# Proto_Pi.net
KiCad netlist of a schematic drawn in EAGLE
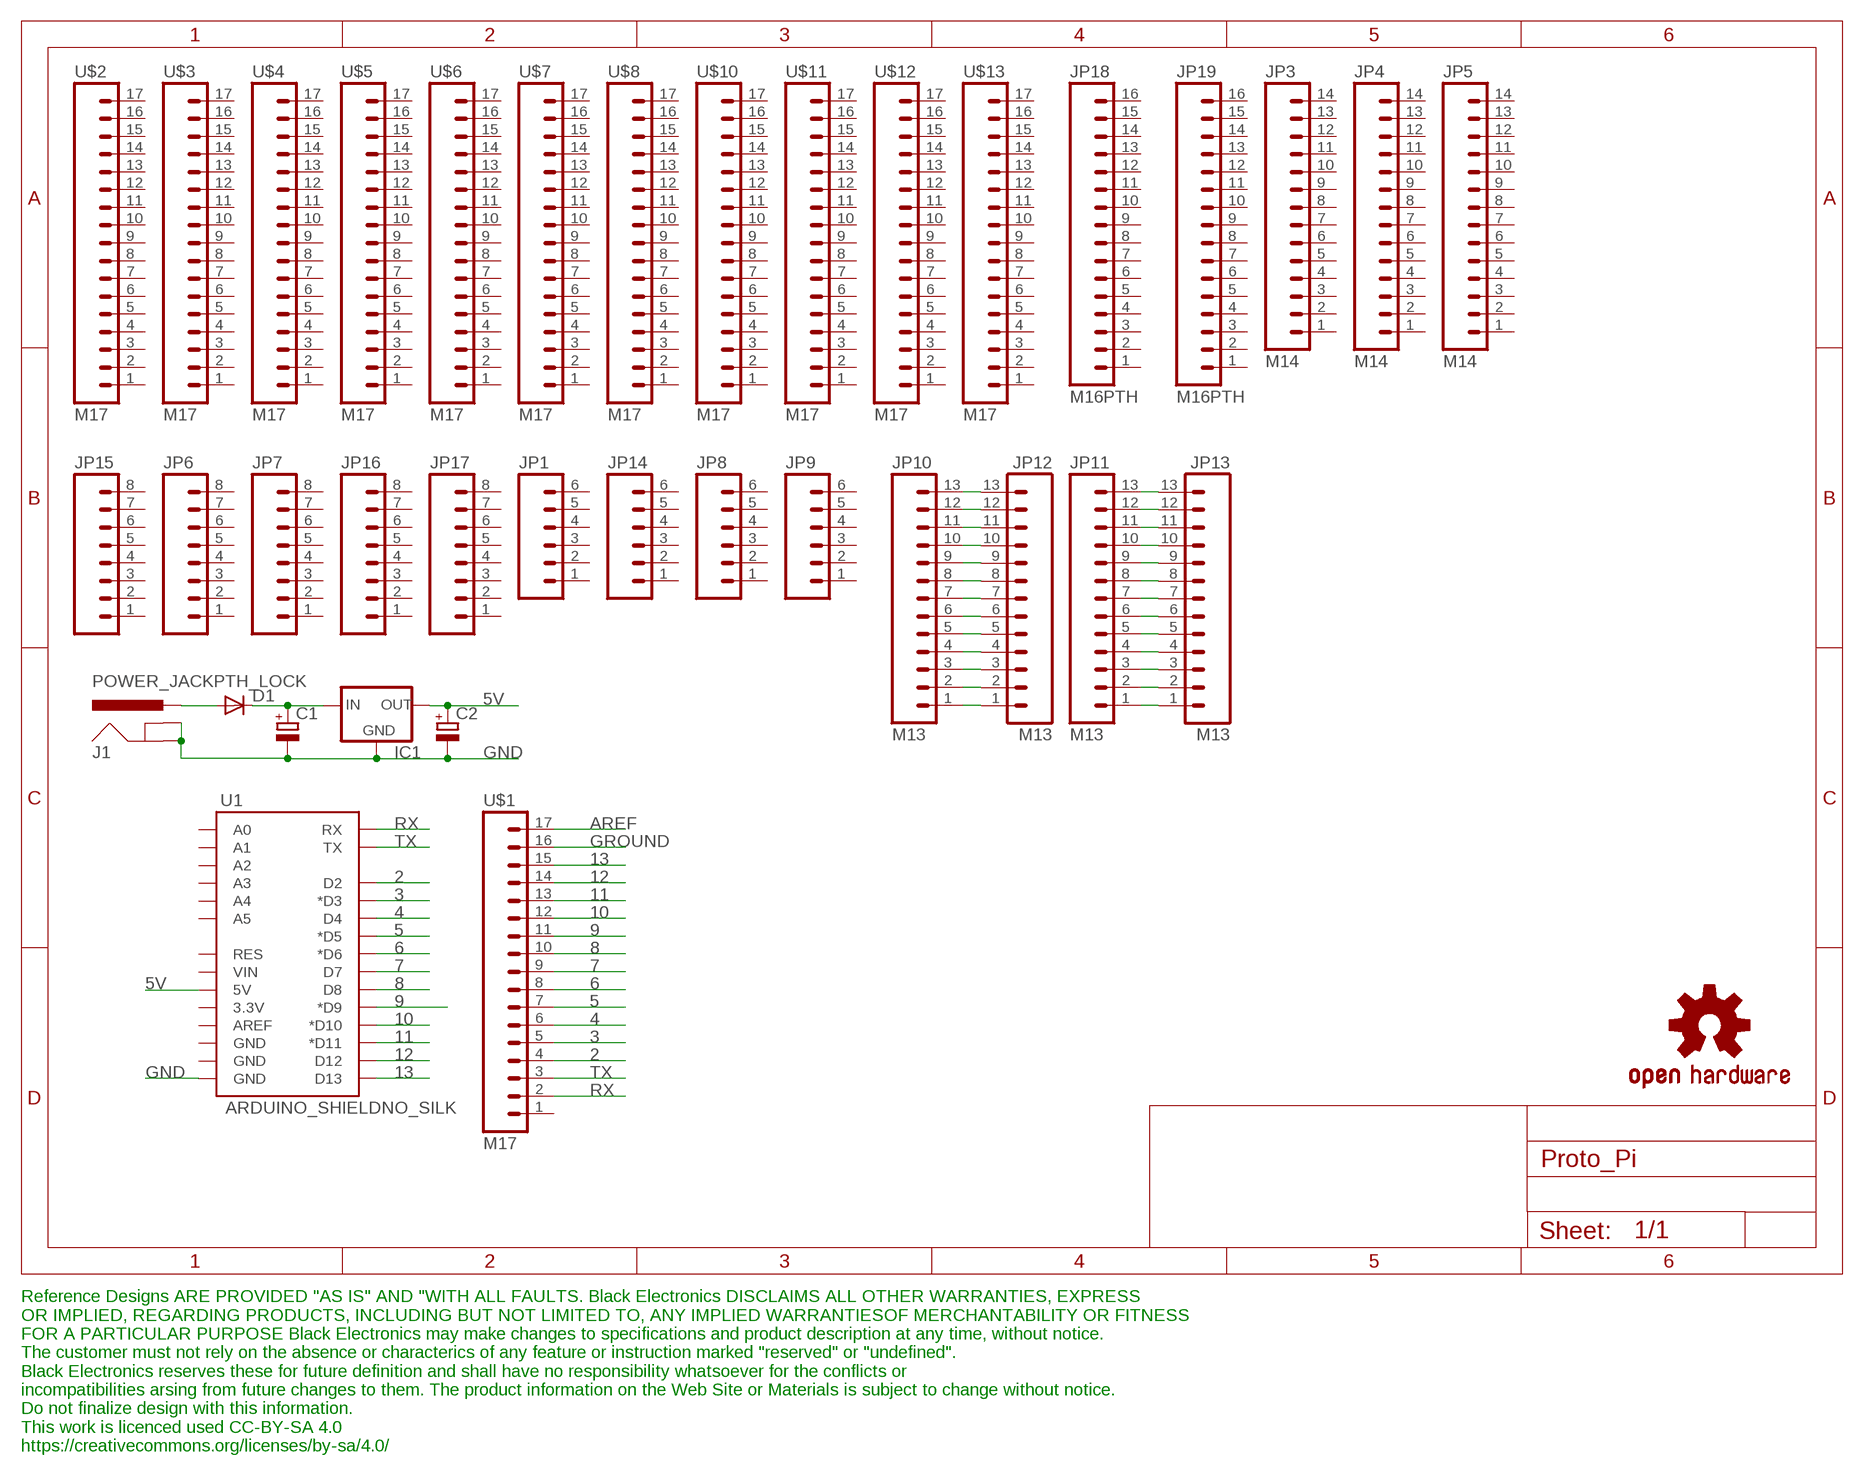
[diagram p0: schematic, sheet 1]

(export (version "E")
  (design (tool "Eeschema 10.0.6"))
  (components
    (comp (ref "C1")
      (value "CPOL-EUE2,5-6E")
      (footprint "eagle-import:E2,5-6E")
      (libsource (lib "eagle-import") (part "CPOL-EUE2,5-6E"))
    )
    (comp (ref "C2")
      (value "CPOL-EUE2.5-7")
      (footprint "eagle-import:E2,5-7")
      (libsource (lib "eagle-import") (part "CPOL-EUE2.5-7"))
    )
    (comp (ref "D1")
      (value "DIODE-C1702-05")
      (footprint "eagle-import:C1702-05")
      (libsource (lib "eagle-import") (part "DIODE-C1702-05"))
    )
    (comp (ref "IC1")
      (value "V_REG_78XXSINK")
      (footprint "eagle-import:TO220-IGO")
      (libsource (lib "eagle-import") (part "V_REG_78XXSINK"))
    )
    (comp (ref "J1")
      (value "POWER_JACKPTH_LOCK")
      (footprint "eagle-import:POWER_JACK_PTH_LOCK")
      (libsource (lib "eagle-import") (part "POWER_JACKPTH_LOCK"))
    )
    (comp (ref "JP1")
      (value "M06SIP")
      (footprint "eagle-import:1X06")
      (libsource (lib "eagle-import") (part "M06SIP"))
    )
    (comp (ref "JP3")
      (value "M14")
      (footprint "eagle-import:1X14")
      (libsource (lib "eagle-import") (part "M14"))
    )
    (comp (ref "JP4")
      (value "M14")
      (footprint "eagle-import:1X14")
      (libsource (lib "eagle-import") (part "M14"))
    )
    (comp (ref "JP5")
      (value "M14")
      (footprint "eagle-import:1X14")
      (libsource (lib "eagle-import") (part "M14"))
    )
    (comp (ref "JP6")
      (value "M081X08")
      (footprint "eagle-import:1X08")
      (libsource (lib "eagle-import") (part "M081X08"))
    )
    (comp (ref "JP7")
      (value "M081X08")
      (footprint "eagle-import:1X08")
      (libsource (lib "eagle-import") (part "M081X08"))
    )
    (comp (ref "JP8")
      (value "M06SIP")
      (footprint "eagle-import:1X06")
      (libsource (lib "eagle-import") (part "M06SIP"))
    )
    (comp (ref "JP9")
      (value "M06SIP")
      (footprint "eagle-import:1X06")
      (libsource (lib "eagle-import") (part "M06SIP"))
    )
    (comp (ref "JP10")
      (value "M13")
      (footprint "eagle-import:1X13")
      (libsource (lib "eagle-import") (part "M13"))
    )
    (comp (ref "JP11")
      (value "M13")
      (footprint "eagle-import:1X13")
      (libsource (lib "eagle-import") (part "M13"))
    )
    (comp (ref "JP12")
      (value "M13")
      (footprint "eagle-import:1X13")
      (libsource (lib "eagle-import") (part "M13"))
    )
    (comp (ref "JP13")
      (value "M13")
      (footprint "eagle-import:1X13")
      (libsource (lib "eagle-import") (part "M13"))
    )
    (comp (ref "JP14")
      (value "M06SIP")
      (footprint "eagle-import:1X06")
      (libsource (lib "eagle-import") (part "M06SIP"))
    )
    (comp (ref "JP15")
      (value "M081X08")
      (footprint "eagle-import:1X08")
      (libsource (lib "eagle-import") (part "M081X08"))
    )
    (comp (ref "JP16")
      (value "M081X08")
      (footprint "eagle-import:1X08")
      (libsource (lib "eagle-import") (part "M081X08"))
    )
    (comp (ref "JP17")
      (value "M081X08")
      (footprint "eagle-import:1X08")
      (libsource (lib "eagle-import") (part "M081X08"))
    )
    (comp (ref "JP18")
      (value "M16PTH")
      (footprint "eagle-import:1X16")
      (libsource (lib "eagle-import") (part "M16PTH"))
    )
    (comp (ref "JP19")
      (value "M16PTH")
      (footprint "eagle-import:1X16")
      (libsource (lib "eagle-import") (part "M16PTH"))
    )
    (comp (ref "U$1")
      (value "M17")
      (footprint "eagle-import:1X17")
      (libsource (lib "eagle-import") (part "M17"))
    )
    (comp (ref "U$2")
      (value "M17")
      (footprint "eagle-import:1X17")
      (libsource (lib "eagle-import") (part "M17"))
    )
    (comp (ref "U$3")
      (value "M17")
      (footprint "eagle-import:1X17")
      (libsource (lib "eagle-import") (part "M17"))
    )
    (comp (ref "U$4")
      (value "M17")
      (footprint "eagle-import:1X17")
      (libsource (lib "eagle-import") (part "M17"))
    )
    (comp (ref "U$5")
      (value "M17")
      (footprint "eagle-import:1X17")
      (libsource (lib "eagle-import") (part "M17"))
    )
    (comp (ref "U$6")
      (value "M17")
      (footprint "eagle-import:1X17")
      (libsource (lib "eagle-import") (part "M17"))
    )
    (comp (ref "U$7")
      (value "M17")
      (footprint "eagle-import:1X17")
      (libsource (lib "eagle-import") (part "M17"))
    )
    (comp (ref "U$8")
      (value "M17")
      (footprint "eagle-import:1X17")
      (libsource (lib "eagle-import") (part "M17"))
    )
    (comp (ref "U$9")
      (value "OSHW-LOGOS")
      (footprint "eagle-import:OSHW-LOGO-S")
      (libsource (lib "eagle-import") (part "OSHW-LOGOS"))
    )
    (comp (ref "U$10")
      (value "M17")
      (footprint "eagle-import:1X17")
      (libsource (lib "eagle-import") (part "M17"))
    )
    (comp (ref "U$11")
      (value "M17")
      (footprint "eagle-import:1X17")
      (libsource (lib "eagle-import") (part "M17"))
    )
    (comp (ref "U$12")
      (value "M17")
      (footprint "eagle-import:1X17")
      (libsource (lib "eagle-import") (part "M17"))
    )
    (comp (ref "U$13")
      (value "M17")
      (footprint "eagle-import:1X17")
      (libsource (lib "eagle-import") (part "M17"))
    )
    (comp (ref "U1")
      (value "ARDUINO_SHIELDNO_SILK")
      (footprint "eagle-import:DUEMILANOVE_VIAS")
      (libsource (lib "eagle-import") (part "ARDUINO_SHIELDNO_SILK"))
    )
  )
  (nets
    (net (code "1") (name "/2") (class "Default")
      (node (ref "U$1") (pin "4") (pinfunction "4_4") (pintype "passive"))
      (node (ref "U1") (pin "D2") (pinfunction "D2_D2") (pintype "bidirectional"))
    )
    (net (code "2") (name "/3") (class "Default")
      (node (ref "U$1") (pin "5") (pinfunction "5_5") (pintype "passive"))
      (node (ref "U1") (pin "D3") (pinfunction "*D3_D3") (pintype "bidirectional"))
    )
    (net (code "3") (name "/4") (class "Default")
      (node (ref "U$1") (pin "6") (pinfunction "6_6") (pintype "passive"))
      (node (ref "U1") (pin "D4") (pinfunction "D4_D4") (pintype "bidirectional"))
    )
    (net (code "4") (name "/5") (class "Default")
      (node (ref "U$1") (pin "7") (pinfunction "7_7") (pintype "passive"))
      (node (ref "U1") (pin "D5") (pinfunction "*D5_D5") (pintype "bidirectional"))
    )
    (net (code "5") (name "/5V") (class "Default")
      (node (ref "C2") (pin "+") (pinfunction "+_+") (pintype "passive"))
      (node (ref "IC1") (pin "OUT") (pinfunction "OUT_OUT") (pintype "output"))
      (node (ref "U1") (pin "5V") (pinfunction "5V_5V") (pintype "bidirectional"))
    )
    (net (code "6") (name "/6") (class "Default")
      (node (ref "U$1") (pin "8") (pinfunction "8_8") (pintype "passive"))
      (node (ref "U1") (pin "D6") (pinfunction "*D6_D6") (pintype "bidirectional"))
    )
    (net (code "7") (name "/7") (class "Default")
      (node (ref "U$1") (pin "9") (pinfunction "9_9") (pintype "passive"))
      (node (ref "U1") (pin "D7") (pinfunction "D7_D7") (pintype "bidirectional"))
    )
    (net (code "8") (name "/8") (class "Default")
      (node (ref "U$1") (pin "10") (pinfunction "10_10") (pintype "passive"))
      (node (ref "U1") (pin "D8") (pinfunction "D8_D8") (pintype "bidirectional"))
    )
    (net (code "9") (name "/9") (class "Default")
      (node (ref "U$1") (pin "11") (pinfunction "11_11") (pintype "passive"))
      (node (ref "U1") (pin "D9") (pinfunction "*D9_D9") (pintype "bidirectional"))
    )
    (net (code "10") (name "/10") (class "Default")
      (node (ref "U$1") (pin "12") (pinfunction "12_12") (pintype "passive"))
      (node (ref "U1") (pin "D10") (pinfunction "*D10_D10") (pintype "bidirectional"))
    )
    (net (code "11") (name "/11") (class "Default")
      (node (ref "U$1") (pin "13") (pinfunction "13_13") (pintype "passive"))
      (node (ref "U1") (pin "D11") (pinfunction "*D11_D11") (pintype "bidirectional"))
    )
    (net (code "12") (name "/12") (class "Default")
      (node (ref "U$1") (pin "14") (pinfunction "14_14") (pintype "passive"))
      (node (ref "U1") (pin "D12") (pinfunction "D12_D12") (pintype "bidirectional"))
    )
    (net (code "13") (name "/13") (class "Default")
      (node (ref "U$1") (pin "15") (pinfunction "15_15") (pintype "passive"))
      (node (ref "U1") (pin "D13") (pinfunction "D13_D13") (pintype "bidirectional"))
    )
    (net (code "14") (name "/AREF") (class "Default")
      (node (ref "U$1") (pin "17") (pinfunction "17_17") (pintype "passive"))
    )
    (net (code "15") (name "/GND") (class "Default")
      (node (ref "C1") (pin "-") (pinfunction "-_-") (pintype "passive"))
      (node (ref "C2") (pin "-") (pinfunction "-_-") (pintype "passive"))
      (node (ref "IC1") (pin "GND") (pinfunction "GND_GND") (pintype "input"))
      (node (ref "J1") (pin "GND") (pinfunction "GND_GND") (pintype "bidirectional"))
      (node (ref "J1") (pin "GNDBREAK") (pinfunction "GNDBREAK_GNDBREAK") (pintype "bidirectional"))
      (node (ref "U1") (pin "GND@0") (pinfunction "GND_GND@0") (pintype "bidirectional"))
    )
    (net (code "16") (name "/GROUND") (class "Default")
      (node (ref "U$1") (pin "16") (pinfunction "16_16") (pintype "passive"))
    )
    (net (code "17") (name "/RX") (class "Default")
      (node (ref "U$1") (pin "2") (pinfunction "2_2") (pintype "passive"))
      (node (ref "U1") (pin "RX") (pinfunction "RX_RX") (pintype "bidirectional"))
    )
    (net (code "18") (name "/TX") (class "Default")
      (node (ref "U$1") (pin "3") (pinfunction "3_3") (pintype "passive"))
      (node (ref "U1") (pin "TX") (pinfunction "TX_TX") (pintype "bidirectional"))
    )
    (net (code "19") (name "Net-(C1-Pad+)") (class "Default")
      (node (ref "C1") (pin "+") (pinfunction "+_+") (pintype "passive"))
      (node (ref "D1") (pin "C") (pinfunction "C_C") (pintype "passive"))
      (node (ref "IC1") (pin "IN") (pinfunction "IN_IN") (pintype "input"))
    )
    (net (code "20") (name "Net-(D1-PadA)") (class "Default")
      (node (ref "D1") (pin "A") (pinfunction "A_A") (pintype "passive"))
      (node (ref "J1") (pin "PWR") (pinfunction "PWR_PWR") (pintype "bidirectional"))
    )
    (net (code "21") (name "Net-(JP10-Pad1)") (class "Default")
      (node (ref "JP10") (pin "1") (pinfunction "1_1") (pintype "passive"))
      (node (ref "JP12") (pin "1") (pinfunction "1_1") (pintype "passive"))
    )
    (net (code "22") (name "Net-(JP10-Pad2)") (class "Default")
      (node (ref "JP10") (pin "2") (pinfunction "2_2") (pintype "passive"))
      (node (ref "JP12") (pin "2") (pinfunction "2_2") (pintype "passive"))
    )
    (net (code "23") (name "Net-(JP10-Pad3)") (class "Default")
      (node (ref "JP10") (pin "3") (pinfunction "3_3") (pintype "passive"))
      (node (ref "JP12") (pin "3") (pinfunction "3_3") (pintype "passive"))
    )
    (net (code "24") (name "Net-(JP10-Pad4)") (class "Default")
      (node (ref "JP10") (pin "4") (pinfunction "4_4") (pintype "passive"))
      (node (ref "JP12") (pin "4") (pinfunction "4_4") (pintype "passive"))
    )
    (net (code "25") (name "Net-(JP10-Pad5)") (class "Default")
      (node (ref "JP10") (pin "5") (pinfunction "5_5") (pintype "passive"))
      (node (ref "JP12") (pin "5") (pinfunction "5_5") (pintype "passive"))
    )
    (net (code "26") (name "Net-(JP10-Pad6)") (class "Default")
      (node (ref "JP10") (pin "6") (pinfunction "6_6") (pintype "passive"))
      (node (ref "JP12") (pin "6") (pinfunction "6_6") (pintype "passive"))
    )
    (net (code "27") (name "Net-(JP10-Pad7)") (class "Default")
      (node (ref "JP10") (pin "7") (pinfunction "7_7") (pintype "passive"))
      (node (ref "JP12") (pin "7") (pinfunction "7_7") (pintype "passive"))
    )
    (net (code "28") (name "Net-(JP10-Pad8)") (class "Default")
      (node (ref "JP10") (pin "8") (pinfunction "8_8") (pintype "passive"))
      (node (ref "JP12") (pin "8") (pinfunction "8_8") (pintype "passive"))
    )
    (net (code "29") (name "Net-(JP10-Pad9)") (class "Default")
      (node (ref "JP10") (pin "9") (pinfunction "9_9") (pintype "passive"))
      (node (ref "JP12") (pin "9") (pinfunction "9_9") (pintype "passive"))
    )
    (net (code "30") (name "Net-(JP10-Pad10)") (class "Default")
      (node (ref "JP10") (pin "10") (pinfunction "10_10") (pintype "passive"))
      (node (ref "JP12") (pin "10") (pinfunction "10_10") (pintype "passive"))
    )
    (net (code "31") (name "Net-(JP10-Pad11)") (class "Default")
      (node (ref "JP10") (pin "11") (pinfunction "11_11") (pintype "passive"))
      (node (ref "JP12") (pin "11") (pinfunction "11_11") (pintype "passive"))
    )
    (net (code "32") (name "Net-(JP10-Pad12)") (class "Default")
      (node (ref "JP10") (pin "12") (pinfunction "12_12") (pintype "passive"))
      (node (ref "JP12") (pin "12") (pinfunction "12_12") (pintype "passive"))
    )
    (net (code "33") (name "Net-(JP10-Pad13)") (class "Default")
      (node (ref "JP10") (pin "13") (pinfunction "13_13") (pintype "passive"))
      (node (ref "JP12") (pin "13") (pinfunction "13_13") (pintype "passive"))
    )
    (net (code "34") (name "Net-(JP11-Pad1)") (class "Default")
      (node (ref "JP11") (pin "1") (pinfunction "1_1") (pintype "passive"))
      (node (ref "JP13") (pin "1") (pinfunction "1_1") (pintype "passive"))
    )
    (net (code "35") (name "Net-(JP11-Pad2)") (class "Default")
      (node (ref "JP11") (pin "2") (pinfunction "2_2") (pintype "passive"))
      (node (ref "JP13") (pin "2") (pinfunction "2_2") (pintype "passive"))
    )
    (net (code "36") (name "Net-(JP11-Pad3)") (class "Default")
      (node (ref "JP11") (pin "3") (pinfunction "3_3") (pintype "passive"))
      (node (ref "JP13") (pin "3") (pinfunction "3_3") (pintype "passive"))
    )
    (net (code "37") (name "Net-(JP11-Pad4)") (class "Default")
      (node (ref "JP11") (pin "4") (pinfunction "4_4") (pintype "passive"))
      (node (ref "JP13") (pin "4") (pinfunction "4_4") (pintype "passive"))
    )
    (net (code "38") (name "Net-(JP11-Pad5)") (class "Default")
      (node (ref "JP11") (pin "5") (pinfunction "5_5") (pintype "passive"))
      (node (ref "JP13") (pin "5") (pinfunction "5_5") (pintype "passive"))
    )
    (net (code "39") (name "Net-(JP11-Pad6)") (class "Default")
      (node (ref "JP11") (pin "6") (pinfunction "6_6") (pintype "passive"))
      (node (ref "JP13") (pin "6") (pinfunction "6_6") (pintype "passive"))
    )
    (net (code "40") (name "Net-(JP11-Pad7)") (class "Default")
      (node (ref "JP11") (pin "7") (pinfunction "7_7") (pintype "passive"))
      (node (ref "JP13") (pin "7") (pinfunction "7_7") (pintype "passive"))
    )
    (net (code "41") (name "Net-(JP11-Pad8)") (class "Default")
      (node (ref "JP11") (pin "8") (pinfunction "8_8") (pintype "passive"))
      (node (ref "JP13") (pin "8") (pinfunction "8_8") (pintype "passive"))
    )
    (net (code "42") (name "Net-(JP11-Pad9)") (class "Default")
      (node (ref "JP11") (pin "9") (pinfunction "9_9") (pintype "passive"))
      (node (ref "JP13") (pin "9") (pinfunction "9_9") (pintype "passive"))
    )
    (net (code "43") (name "Net-(JP11-Pad10)") (class "Default")
      (node (ref "JP11") (pin "10") (pinfunction "10_10") (pintype "passive"))
      (node (ref "JP13") (pin "10") (pinfunction "10_10") (pintype "passive"))
    )
    (net (code "44") (name "Net-(JP11-Pad11)") (class "Default")
      (node (ref "JP11") (pin "11") (pinfunction "11_11") (pintype "passive"))
      (node (ref "JP13") (pin "11") (pinfunction "11_11") (pintype "passive"))
    )
    (net (code "45") (name "Net-(JP11-Pad12)") (class "Default")
      (node (ref "JP11") (pin "12") (pinfunction "12_12") (pintype "passive"))
      (node (ref "JP13") (pin "12") (pinfunction "12_12") (pintype "passive"))
    )
    (net (code "46") (name "Net-(JP11-Pad13)") (class "Default")
      (node (ref "JP11") (pin "13") (pinfunction "13_13") (pintype "passive"))
      (node (ref "JP13") (pin "13") (pinfunction "13_13") (pintype "passive"))
    )
    (net (code "47") (name "unconnected-(JP1-Pad1)") (class "Default")
      (node (ref "JP1") (pin "1") (pinfunction "1_1") (pintype "passive"))
    )
    (net (code "48") (name "unconnected-(JP1-Pad2)") (class "Default")
      (node (ref "JP1") (pin "2") (pinfunction "2_2") (pintype "passive"))
    )
    (net (code "49") (name "unconnected-(JP1-Pad3)") (class "Default")
      (node (ref "JP1") (pin "3") (pinfunction "3_3") (pintype "passive"))
    )
    (net (code "50") (name "unconnected-(JP1-Pad4)") (class "Default")
      (node (ref "JP1") (pin "4") (pinfunction "4_4") (pintype "passive"))
    )
    (net (code "51") (name "unconnected-(JP1-Pad5)") (class "Default")
      (node (ref "JP1") (pin "5") (pinfunction "5_5") (pintype "passive"))
    )
    (net (code "52") (name "unconnected-(JP1-Pad6)") (class "Default")
      (node (ref "JP1") (pin "6") (pinfunction "6_6") (pintype "passive"))
    )
    (net (code "53") (name "unconnected-(JP3-Pad1)") (class "Default")
      (node (ref "JP3") (pin "1") (pinfunction "1_1") (pintype "passive"))
    )
    (net (code "54") (name "unconnected-(JP3-Pad2)") (class "Default")
      (node (ref "JP3") (pin "2") (pinfunction "2_2") (pintype "passive"))
    )
    (net (code "55") (name "unconnected-(JP3-Pad3)") (class "Default")
      (node (ref "JP3") (pin "3") (pinfunction "3_3") (pintype "passive"))
    )
    (net (code "56") (name "unconnected-(JP3-Pad4)") (class "Default")
      (node (ref "JP3") (pin "4") (pinfunction "4_4") (pintype "passive"))
    )
    (net (code "57") (name "unconnected-(JP3-Pad5)") (class "Default")
      (node (ref "JP3") (pin "5") (pinfunction "5_5") (pintype "passive"))
    )
    (net (code "58") (name "unconnected-(JP3-Pad6)") (class "Default")
      (node (ref "JP3") (pin "6") (pinfunction "6_6") (pintype "passive"))
    )
    (net (code "59") (name "unconnected-(JP3-Pad7)") (class "Default")
      (node (ref "JP3") (pin "7") (pinfunction "7_7") (pintype "passive"))
    )
    (net (code "60") (name "unconnected-(JP3-Pad8)") (class "Default")
      (node (ref "JP3") (pin "8") (pinfunction "8_8") (pintype "passive"))
    )
    (net (code "61") (name "unconnected-(JP3-Pad9)") (class "Default")
      (node (ref "JP3") (pin "9") (pinfunction "9_9") (pintype "passive"))
    )
    (net (code "62") (name "unconnected-(JP3-Pad10)") (class "Default")
      (node (ref "JP3") (pin "10") (pinfunction "10_10") (pintype "passive"))
    )
    (net (code "63") (name "unconnected-(JP3-Pad11)") (class "Default")
      (node (ref "JP3") (pin "11") (pinfunction "11_11") (pintype "passive"))
    )
    (net (code "64") (name "unconnected-(JP3-Pad12)") (class "Default")
      (node (ref "JP3") (pin "12") (pinfunction "12_12") (pintype "passive"))
    )
    (net (code "65") (name "unconnected-(JP3-Pad13)") (class "Default")
      (node (ref "JP3") (pin "13") (pinfunction "13_13") (pintype "passive"))
    )
    (net (code "66") (name "unconnected-(JP3-Pad14)") (class "Default")
      (node (ref "JP3") (pin "14") (pinfunction "14_14") (pintype "passive"))
    )
    (net (code "67") (name "unconnected-(JP4-Pad1)") (class "Default")
      (node (ref "JP4") (pin "1") (pinfunction "1_1") (pintype "passive"))
    )
    (net (code "68") (name "unconnected-(JP4-Pad2)") (class "Default")
      (node (ref "JP4") (pin "2") (pinfunction "2_2") (pintype "passive"))
    )
    (net (code "69") (name "unconnected-(JP4-Pad3)") (class "Default")
      (node (ref "JP4") (pin "3") (pinfunction "3_3") (pintype "passive"))
    )
    (net (code "70") (name "unconnected-(JP4-Pad4)") (class "Default")
      (node (ref "JP4") (pin "4") (pinfunction "4_4") (pintype "passive"))
    )
    (net (code "71") (name "unconnected-(JP4-Pad5)") (class "Default")
      (node (ref "JP4") (pin "5") (pinfunction "5_5") (pintype "passive"))
    )
    (net (code "72") (name "unconnected-(JP4-Pad6)") (class "Default")
      (node (ref "JP4") (pin "6") (pinfunction "6_6") (pintype "passive"))
    )
    (net (code "73") (name "unconnected-(JP4-Pad7)") (class "Default")
      (node (ref "JP4") (pin "7") (pinfunction "7_7") (pintype "passive"))
    )
    (net (code "74") (name "unconnected-(JP4-Pad8)") (class "Default")
      (node (ref "JP4") (pin "8") (pinfunction "8_8") (pintype "passive"))
    )
    (net (code "75") (name "unconnected-(JP4-Pad9)") (class "Default")
      (node (ref "JP4") (pin "9") (pinfunction "9_9") (pintype "passive"))
    )
    (net (code "76") (name "unconnected-(JP4-Pad10)") (class "Default")
      (node (ref "JP4") (pin "10") (pinfunction "10_10") (pintype "passive"))
    )
    (net (code "77") (name "unconnected-(JP4-Pad11)") (class "Default")
      (node (ref "JP4") (pin "11") (pinfunction "11_11") (pintype "passive"))
    )
    (net (code "78") (name "unconnected-(JP4-Pad12)") (class "Default")
      (node (ref "JP4") (pin "12") (pinfunction "12_12") (pintype "passive"))
    )
    (net (code "79") (name "unconnected-(JP4-Pad13)") (class "Default")
      (node (ref "JP4") (pin "13") (pinfunction "13_13") (pintype "passive"))
    )
    (net (code "80") (name "unconnected-(JP4-Pad14)") (class "Default")
      (node (ref "JP4") (pin "14") (pinfunction "14_14") (pintype "passive"))
    )
    (net (code "81") (name "unconnected-(JP5-Pad1)") (class "Default")
      (node (ref "JP5") (pin "1") (pinfunction "1_1") (pintype "passive"))
    )
    (net (code "82") (name "unconnected-(JP5-Pad2)") (class "Default")
      (node (ref "JP5") (pin "2") (pinfunction "2_2") (pintype "passive"))
    )
    (net (code "83") (name "unconnected-(JP5-Pad3)") (class "Default")
      (node (ref "JP5") (pin "3") (pinfunction "3_3") (pintype "passive"))
    )
    (net (code "84") (name "unconnected-(JP5-Pad4)") (class "Default")
      (node (ref "JP5") (pin "4") (pinfunction "4_4") (pintype "passive"))
    )
    (net (code "85") (name "unconnected-(JP5-Pad5)") (class "Default")
      (node (ref "JP5") (pin "5") (pinfunction "5_5") (pintype "passive"))
    )
    (net (code "86") (name "unconnected-(JP5-Pad6)") (class "Default")
      (node (ref "JP5") (pin "6") (pinfunction "6_6") (pintype "passive"))
    )
    (net (code "87") (name "unconnected-(JP5-Pad7)") (class "Default")
      (node (ref "JP5") (pin "7") (pinfunction "7_7") (pintype "passive"))
    )
    (net (code "88") (name "unconnected-(JP5-Pad8)") (class "Default")
      (node (ref "JP5") (pin "8") (pinfunction "8_8") (pintype "passive"))
    )
    (net (code "89") (name "unconnected-(JP5-Pad9)") (class "Default")
      (node (ref "JP5") (pin "9") (pinfunction "9_9") (pintype "passive"))
    )
    (net (code "90") (name "unconnected-(JP5-Pad10)") (class "Default")
      (node (ref "JP5") (pin "10") (pinfunction "10_10") (pintype "passive"))
    )
    (net (code "91") (name "unconnected-(JP5-Pad11)") (class "Default")
      (node (ref "JP5") (pin "11") (pinfunction "11_11") (pintype "passive"))
    )
    (net (code "92") (name "unconnected-(JP5-Pad12)") (class "Default")
      (node (ref "JP5") (pin "12") (pinfunction "12_12") (pintype "passive"))
    )
    (net (code "93") (name "unconnected-(JP5-Pad13)") (class "Default")
      (node (ref "JP5") (pin "13") (pinfunction "13_13") (pintype "passive"))
    )
    (net (code "94") (name "unconnected-(JP5-Pad14)") (class "Default")
      (node (ref "JP5") (pin "14") (pinfunction "14_14") (pintype "passive"))
    )
    (net (code "95") (name "unconnected-(JP6-Pad1)") (class "Default")
      (node (ref "JP6") (pin "1") (pinfunction "1_1") (pintype "passive"))
    )
    (net (code "96") (name "unconnected-(JP6-Pad2)") (class "Default")
      (node (ref "JP6") (pin "2") (pinfunction "2_2") (pintype "passive"))
    )
    (net (code "97") (name "unconnected-(JP6-Pad3)") (class "Default")
      (node (ref "JP6") (pin "3") (pinfunction "3_3") (pintype "passive"))
    )
    (net (code "98") (name "unconnected-(JP6-Pad4)") (class "Default")
      (node (ref "JP6") (pin "4") (pinfunction "4_4") (pintype "passive"))
    )
    (net (code "99") (name "unconnected-(JP6-Pad5)") (class "Default")
      (node (ref "JP6") (pin "5") (pinfunction "5_5") (pintype "passive"))
    )
    (net (code "100") (name "unconnected-(JP6-Pad6)") (class "Default")
      (node (ref "JP6") (pin "6") (pinfunction "6_6") (pintype "passive"))
    )
    (net (code "101") (name "unconnected-(JP6-Pad7)") (class "Default")
      (node (ref "JP6") (pin "7") (pinfunction "7_7") (pintype "passive"))
    )
    (net (code "102") (name "unconnected-(JP6-Pad8)") (class "Default")
      (node (ref "JP6") (pin "8") (pinfunction "8_8") (pintype "passive"))
    )
    (net (code "103") (name "unconnected-(JP7-Pad1)") (class "Default")
      (node (ref "JP7") (pin "1") (pinfunction "1_1") (pintype "passive"))
    )
    (net (code "104") (name "unconnected-(JP7-Pad2)") (class "Default")
      (node (ref "JP7") (pin "2") (pinfunction "2_2") (pintype "passive"))
    )
    (net (code "105") (name "unconnected-(JP7-Pad3)") (class "Default")
      (node (ref "JP7") (pin "3") (pinfunction "3_3") (pintype "passive"))
    )
    (net (code "106") (name "unconnected-(JP7-Pad4)") (class "Default")
      (node (ref "JP7") (pin "4") (pinfunction "4_4") (pintype "passive"))
    )
    (net (code "107") (name "unconnected-(JP7-Pad5)") (class "Default")
      (node (ref "JP7") (pin "5") (pinfunction "5_5") (pintype "passive"))
    )
    (net (code "108") (name "unconnected-(JP7-Pad6)") (class "Default")
      (node (ref "JP7") (pin "6") (pinfunction "6_6") (pintype "passive"))
    )
    (net (code "109") (name "unconnected-(JP7-Pad7)") (class "Default")
      (node (ref "JP7") (pin "7") (pinfunction "7_7") (pintype "passive"))
    )
    (net (code "110") (name "unconnected-(JP7-Pad8)") (class "Default")
      (node (ref "JP7") (pin "8") (pinfunction "8_8") (pintype "passive"))
    )
    (net (code "111") (name "unconnected-(JP8-Pad1)") (class "Default")
      (node (ref "JP8") (pin "1") (pinfunction "1_1") (pintype "passive"))
    )
    (net (code "112") (name "unconnected-(JP8-Pad2)") (class "Default")
      (node (ref "JP8") (pin "2") (pinfunction "2_2") (pintype "passive"))
    )
    (net (code "113") (name "unconnected-(JP8-Pad3)") (class "Default")
      (node (ref "JP8") (pin "3") (pinfunction "3_3") (pintype "passive"))
    )
    (net (code "114") (name "unconnected-(JP8-Pad4)") (class "Default")
      (node (ref "JP8") (pin "4") (pinfunction "4_4") (pintype "passive"))
    )
    (net (code "115") (name "unconnected-(JP8-Pad5)") (class "Default")
      (node (ref "JP8") (pin "5") (pinfunction "5_5") (pintype "passive"))
    )
    (net (code "116") (name "unconnected-(JP8-Pad6)") (class "Default")
      (node (ref "JP8") (pin "6") (pinfunction "6_6") (pintype "passive"))
    )
    (net (code "117") (name "unconnected-(JP9-Pad1)") (class "Default")
      (node (ref "JP9") (pin "1") (pinfunction "1_1") (pintype "passive"))
    )
    (net (code "118") (name "unconnected-(JP9-Pad2)") (class "Default")
      (node (ref "JP9") (pin "2") (pinfunction "2_2") (pintype "passive"))
    )
    (net (code "119") (name "unconnected-(JP9-Pad3)") (class "Default")
      (node (ref "JP9") (pin "3") (pinfunction "3_3") (pintype "passive"))
    )
    (net (code "120") (name "unconnected-(JP9-Pad4)") (class "Default")
      (node (ref "JP9") (pin "4") (pinfunction "4_4") (pintype "passive"))
    )
    (net (code "121") (name "unconnected-(JP9-Pad5)") (class "Default")
      (node (ref "JP9") (pin "5") (pinfunction "5_5") (pintype "passive"))
    )
    (net (code "122") (name "unconnected-(JP9-Pad6)") (class "Default")
      (node (ref "JP9") (pin "6") (pinfunction "6_6") (pintype "passive"))
    )
    (net (code "123") (name "unconnected-(JP14-Pad1)") (class "Default")
      (node (ref "JP14") (pin "1") (pinfunction "1_1") (pintype "passive"))
    )
    (net (code "124") (name "unconnected-(JP14-Pad2)") (class "Default")
      (node (ref "JP14") (pin "2") (pinfunction "2_2") (pintype "passive"))
    )
    (net (code "125") (name "unconnected-(JP14-Pad3)") (class "Default")
      (node (ref "JP14") (pin "3") (pinfunction "3_3") (pintype "passive"))
    )
    (net (code "126") (name "unconnected-(JP14-Pad4)") (class "Default")
      (node (ref "JP14") (pin "4") (pinfunction "4_4") (pintype "passive"))
    )
    (net (code "127") (name "unconnected-(JP14-Pad5)") (class "Default")
      (node (ref "JP14") (pin "5") (pinfunction "5_5") (pintype "passive"))
    )
    (net (code "128") (name "unconnected-(JP14-Pad6)") (class "Default")
      (node (ref "JP14") (pin "6") (pinfunction "6_6") (pintype "passive"))
    )
    (net (code "129") (name "unconnected-(JP15-Pad1)") (class "Default")
      (node (ref "JP15") (pin "1") (pinfunction "1_1") (pintype "passive"))
    )
    (net (code "130") (name "unconnected-(JP15-Pad2)") (class "Default")
      (node (ref "JP15") (pin "2") (pinfunction "2_2") (pintype "passive"))
    )
    (net (code "131") (name "unconnected-(JP15-Pad3)") (class "Default")
      (node (ref "JP15") (pin "3") (pinfunction "3_3") (pintype "passive"))
    )
    (net (code "132") (name "unconnected-(JP15-Pad4)") (class "Default")
      (node (ref "JP15") (pin "4") (pinfunction "4_4") (pintype "passive"))
    )
    (net (code "133") (name "unconnected-(JP15-Pad5)") (class "Default")
      (node (ref "JP15") (pin "5") (pinfunction "5_5") (pintype "passive"))
    )
    (net (code "134") (name "unconnected-(JP15-Pad6)") (class "Default")
      (node (ref "JP15") (pin "6") (pinfunction "6_6") (pintype "passive"))
    )
    (net (code "135") (name "unconnected-(JP15-Pad7)") (class "Default")
      (node (ref "JP15") (pin "7") (pinfunction "7_7") (pintype "passive"))
    )
    (net (code "136") (name "unconnected-(JP15-Pad8)") (class "Default")
      (node (ref "JP15") (pin "8") (pinfunction "8_8") (pintype "passive"))
    )
    (net (code "137") (name "unconnected-(JP16-Pad1)") (class "Default")
      (node (ref "JP16") (pin "1") (pinfunction "1_1") (pintype "passive"))
    )
    (net (code "138") (name "unconnected-(JP16-Pad2)") (class "Default")
      (node (ref "JP16") (pin "2") (pinfunction "2_2") (pintype "passive"))
    )
    (net (code "139") (name "unconnected-(JP16-Pad3)") (class "Default")
      (node (ref "JP16") (pin "3") (pinfunction "3_3") (pintype "passive"))
    )
    (net (code "140") (name "unconnected-(JP16-Pad4)") (class "Default")
      (node (ref "JP16") (pin "4") (pinfunction "4_4") (pintype "passive"))
    )
    (net (code "141") (name "unconnected-(JP16-Pad5)") (class "Default")
      (node (ref "JP16") (pin "5") (pinfunction "5_5") (pintype "passive"))
    )
    (net (code "142") (name "unconnected-(JP16-Pad6)") (class "Default")
      (node (ref "JP16") (pin "6") (pinfunction "6_6") (pintype "passive"))
    )
    (net (code "143") (name "unconnected-(JP16-Pad7)") (class "Default")
      (node (ref "JP16") (pin "7") (pinfunction "7_7") (pintype "passive"))
    )
    (net (code "144") (name "unconnected-(JP16-Pad8)") (class "Default")
      (node (ref "JP16") (pin "8") (pinfunction "8_8") (pintype "passive"))
    )
    (net (code "145") (name "unconnected-(JP17-Pad1)") (class "Default")
      (node (ref "JP17") (pin "1") (pinfunction "1_1") (pintype "passive"))
    )
    (net (code "146") (name "unconnected-(JP17-Pad2)") (class "Default")
      (node (ref "JP17") (pin "2") (pinfunction "2_2") (pintype "passive"))
    )
    (net (code "147") (name "unconnected-(JP17-Pad3)") (class "Default")
      (node (ref "JP17") (pin "3") (pinfunction "3_3") (pintype "passive"))
    )
    (net (code "148") (name "unconnected-(JP17-Pad4)") (class "Default")
      (node (ref "JP17") (pin "4") (pinfunction "4_4") (pintype "passive"))
    )
    (net (code "149") (name "unconnected-(JP17-Pad5)") (class "Default")
      (node (ref "JP17") (pin "5") (pinfunction "5_5") (pintype "passive"))
    )
    (net (code "150") (name "unconnected-(JP17-Pad6)") (class "Default")
      (node (ref "JP17") (pin "6") (pinfunction "6_6") (pintype "passive"))
    )
    (net (code "151") (name "unconnected-(JP17-Pad7)") (class "Default")
      (node (ref "JP17") (pin "7") (pinfunction "7_7") (pintype "passive"))
    )
    (net (code "152") (name "unconnected-(JP17-Pad8)") (class "Default")
      (node (ref "JP17") (pin "8") (pinfunction "8_8") (pintype "passive"))
    )
    (net (code "153") (name "unconnected-(JP18-Pad1)") (class "Default")
      (node (ref "JP18") (pin "1") (pinfunction "1_1") (pintype "passive"))
    )
    (net (code "154") (name "unconnected-(JP18-Pad2)") (class "Default")
      (node (ref "JP18") (pin "2") (pinfunction "2_2") (pintype "passive"))
    )
    (net (code "155") (name "unconnected-(JP18-Pad3)") (class "Default")
      (node (ref "JP18") (pin "3") (pinfunction "3_3") (pintype "passive"))
    )
    (net (code "156") (name "unconnected-(JP18-Pad4)") (class "Default")
      (node (ref "JP18") (pin "4") (pinfunction "4_4") (pintype "passive"))
    )
    (net (code "157") (name "unconnected-(JP18-Pad5)") (class "Default")
      (node (ref "JP18") (pin "5") (pinfunction "5_5") (pintype "passive"))
    )
    (net (code "158") (name "unconnected-(JP18-Pad6)") (class "Default")
      (node (ref "JP18") (pin "6") (pinfunction "6_6") (pintype "passive"))
    )
    (net (code "159") (name "unconnected-(JP18-Pad7)") (class "Default")
      (node (ref "JP18") (pin "7") (pinfunction "7_7") (pintype "passive"))
    )
    (net (code "160") (name "unconnected-(JP18-Pad8)") (class "Default")
      (node (ref "JP18") (pin "8") (pinfunction "8_8") (pintype "passive"))
    )
    (net (code "161") (name "unconnected-(JP18-Pad9)") (class "Default")
      (node (ref "JP18") (pin "9") (pinfunction "9_9") (pintype "passive"))
    )
    (net (code "162") (name "unconnected-(JP18-Pad10)") (class "Default")
      (node (ref "JP18") (pin "10") (pinfunction "10_10") (pintype "passive"))
    )
    (net (code "163") (name "unconnected-(JP18-Pad11)") (class "Default")
      (node (ref "JP18") (pin "11") (pinfunction "11_11") (pintype "passive"))
    )
    (net (code "164") (name "unconnected-(JP18-Pad12)") (class "Default")
      (node (ref "JP18") (pin "12") (pinfunction "12_12") (pintype "passive"))
    )
    (net (code "165") (name "unconnected-(JP18-Pad13)") (class "Default")
      (node (ref "JP18") (pin "13") (pinfunction "13_13") (pintype "passive"))
    )
    (net (code "166") (name "unconnected-(JP18-Pad14)") (class "Default")
      (node (ref "JP18") (pin "14") (pinfunction "14_14") (pintype "passive"))
    )
    (net (code "167") (name "unconnected-(JP18-Pad15)") (class "Default")
      (node (ref "JP18") (pin "15") (pinfunction "15_15") (pintype "passive"))
    )
    (net (code "168") (name "unconnected-(JP18-Pad16)") (class "Default")
      (node (ref "JP18") (pin "16") (pinfunction "16_16") (pintype "passive"))
    )
    (net (code "169") (name "unconnected-(JP19-Pad1)") (class "Default")
      (node (ref "JP19") (pin "1") (pinfunction "1_1") (pintype "passive"))
    )
    (net (code "170") (name "unconnected-(JP19-Pad2)") (class "Default")
      (node (ref "JP19") (pin "2") (pinfunction "2_2") (pintype "passive"))
    )
    (net (code "171") (name "unconnected-(JP19-Pad3)") (class "Default")
      (node (ref "JP19") (pin "3") (pinfunction "3_3") (pintype "passive"))
    )
    (net (code "172") (name "unconnected-(JP19-Pad4)") (class "Default")
      (node (ref "JP19") (pin "4") (pinfunction "4_4") (pintype "passive"))
    )
    (net (code "173") (name "unconnected-(JP19-Pad5)") (class "Default")
      (node (ref "JP19") (pin "5") (pinfunction "5_5") (pintype "passive"))
    )
    (net (code "174") (name "unconnected-(JP19-Pad6)") (class "Default")
      (node (ref "JP19") (pin "6") (pinfunction "6_6") (pintype "passive"))
    )
    (net (code "175") (name "unconnected-(JP19-Pad7)") (class "Default")
      (node (ref "JP19") (pin "7") (pinfunction "7_7") (pintype "passive"))
    )
    (net (code "176") (name "unconnected-(JP19-Pad8)") (class "Default")
      (node (ref "JP19") (pin "8") (pinfunction "8_8") (pintype "passive"))
    )
    (net (code "177") (name "unconnected-(JP19-Pad9)") (class "Default")
      (node (ref "JP19") (pin "9") (pinfunction "9_9") (pintype "passive"))
    )
    (net (code "178") (name "unconnected-(JP19-Pad10)") (class "Default")
      (node (ref "JP19") (pin "10") (pinfunction "10_10") (pintype "passive"))
    )
    (net (code "179") (name "unconnected-(JP19-Pad11)") (class "Default")
      (node (ref "JP19") (pin "11") (pinfunction "11_11") (pintype "passive"))
    )
    (net (code "180") (name "unconnected-(JP19-Pad12)") (class "Default")
      (node (ref "JP19") (pin "12") (pinfunction "12_12") (pintype "passive"))
    )
    (net (code "181") (name "unconnected-(JP19-Pad13)") (class "Default")
      (node (ref "JP19") (pin "13") (pinfunction "13_13") (pintype "passive"))
    )
    (net (code "182") (name "unconnected-(JP19-Pad14)") (class "Default")
      (node (ref "JP19") (pin "14") (pinfunction "14_14") (pintype "passive"))
    )
    (net (code "183") (name "unconnected-(JP19-Pad15)") (class "Default")
      (node (ref "JP19") (pin "15") (pinfunction "15_15") (pintype "passive"))
    )
    (net (code "184") (name "unconnected-(JP19-Pad16)") (class "Default")
      (node (ref "JP19") (pin "16") (pinfunction "16_16") (pintype "passive"))
    )
    (net (code "185") (name "unconnected-(U$1-Pad1)") (class "Default")
      (node (ref "U$1") (pin "1") (pinfunction "1_1") (pintype "passive"))
    )
    (net (code "186") (name "unconnected-(U$2-Pad1)") (class "Default")
      (node (ref "U$2") (pin "1") (pinfunction "1_1") (pintype "passive"))
    )
    (net (code "187") (name "unconnected-(U$2-Pad2)") (class "Default")
      (node (ref "U$2") (pin "2") (pinfunction "2_2") (pintype "passive"))
    )
    (net (code "188") (name "unconnected-(U$2-Pad3)") (class "Default")
      (node (ref "U$2") (pin "3") (pinfunction "3_3") (pintype "passive"))
    )
    (net (code "189") (name "unconnected-(U$2-Pad4)") (class "Default")
      (node (ref "U$2") (pin "4") (pinfunction "4_4") (pintype "passive"))
    )
    (net (code "190") (name "unconnected-(U$2-Pad5)") (class "Default")
      (node (ref "U$2") (pin "5") (pinfunction "5_5") (pintype "passive"))
    )
    (net (code "191") (name "unconnected-(U$2-Pad6)") (class "Default")
      (node (ref "U$2") (pin "6") (pinfunction "6_6") (pintype "passive"))
    )
    (net (code "192") (name "unconnected-(U$2-Pad7)") (class "Default")
      (node (ref "U$2") (pin "7") (pinfunction "7_7") (pintype "passive"))
    )
    (net (code "193") (name "unconnected-(U$2-Pad8)") (class "Default")
      (node (ref "U$2") (pin "8") (pinfunction "8_8") (pintype "passive"))
    )
    (net (code "194") (name "unconnected-(U$2-Pad9)") (class "Default")
      (node (ref "U$2") (pin "9") (pinfunction "9_9") (pintype "passive"))
    )
    (net (code "195") (name "unconnected-(U$2-Pad10)") (class "Default")
      (node (ref "U$2") (pin "10") (pinfunction "10_10") (pintype "passive"))
    )
    (net (code "196") (name "unconnected-(U$2-Pad11)") (class "Default")
      (node (ref "U$2") (pin "11") (pinfunction "11_11") (pintype "passive"))
    )
    (net (code "197") (name "unconnected-(U$2-Pad12)") (class "Default")
      (node (ref "U$2") (pin "12") (pinfunction "12_12") (pintype "passive"))
    )
    (net (code "198") (name "unconnected-(U$2-Pad13)") (class "Default")
      (node (ref "U$2") (pin "13") (pinfunction "13_13") (pintype "passive"))
    )
    (net (code "199") (name "unconnected-(U$2-Pad14)") (class "Default")
      (node (ref "U$2") (pin "14") (pinfunction "14_14") (pintype "passive"))
    )
    (net (code "200") (name "unconnected-(U$2-Pad15)") (class "Default")
      (node (ref "U$2") (pin "15") (pinfunction "15_15") (pintype "passive"))
    )
    (net (code "201") (name "unconnected-(U$2-Pad16)") (class "Default")
      (node (ref "U$2") (pin "16") (pinfunction "16_16") (pintype "passive"))
    )
    (net (code "202") (name "unconnected-(U$2-Pad17)") (class "Default")
      (node (ref "U$2") (pin "17") (pinfunction "17_17") (pintype "passive"))
    )
    (net (code "203") (name "unconnected-(U$3-Pad1)") (class "Default")
      (node (ref "U$3") (pin "1") (pinfunction "1_1") (pintype "passive"))
    )
    (net (code "204") (name "unconnected-(U$3-Pad2)") (class "Default")
      (node (ref "U$3") (pin "2") (pinfunction "2_2") (pintype "passive"))
    )
    (net (code "205") (name "unconnected-(U$3-Pad3)") (class "Default")
      (node (ref "U$3") (pin "3") (pinfunction "3_3") (pintype "passive"))
    )
    (net (code "206") (name "unconnected-(U$3-Pad4)") (class "Default")
      (node (ref "U$3") (pin "4") (pinfunction "4_4") (pintype "passive"))
    )
    (net (code "207") (name "unconnected-(U$3-Pad5)") (class "Default")
      (node (ref "U$3") (pin "5") (pinfunction "5_5") (pintype "passive"))
    )
    (net (code "208") (name "unconnected-(U$3-Pad6)") (class "Default")
      (node (ref "U$3") (pin "6") (pinfunction "6_6") (pintype "passive"))
    )
    (net (code "209") (name "unconnected-(U$3-Pad7)") (class "Default")
      (node (ref "U$3") (pin "7") (pinfunction "7_7") (pintype "passive"))
    )
    (net (code "210") (name "unconnected-(U$3-Pad8)") (class "Default")
      (node (ref "U$3") (pin "8") (pinfunction "8_8") (pintype "passive"))
    )
    (net (code "211") (name "unconnected-(U$3-Pad9)") (class "Default")
      (node (ref "U$3") (pin "9") (pinfunction "9_9") (pintype "passive"))
    )
    (net (code "212") (name "unconnected-(U$3-Pad10)") (class "Default")
      (node (ref "U$3") (pin "10") (pinfunction "10_10") (pintype "passive"))
    )
    (net (code "213") (name "unconnected-(U$3-Pad11)") (class "Default")
      (node (ref "U$3") (pin "11") (pinfunction "11_11") (pintype "passive"))
    )
    (net (code "214") (name "unconnected-(U$3-Pad12)") (class "Default")
      (node (ref "U$3") (pin "12") (pinfunction "12_12") (pintype "passive"))
    )
    (net (code "215") (name "unconnected-(U$3-Pad13)") (class "Default")
      (node (ref "U$3") (pin "13") (pinfunction "13_13") (pintype "passive"))
    )
    (net (code "216") (name "unconnected-(U$3-Pad14)") (class "Default")
      (node (ref "U$3") (pin "14") (pinfunction "14_14") (pintype "passive"))
    )
    (net (code "217") (name "unconnected-(U$3-Pad15)") (class "Default")
      (node (ref "U$3") (pin "15") (pinfunction "15_15") (pintype "passive"))
    )
    (net (code "218") (name "unconnected-(U$3-Pad16)") (class "Default")
      (node (ref "U$3") (pin "16") (pinfunction "16_16") (pintype "passive"))
    )
    (net (code "219") (name "unconnected-(U$3-Pad17)") (class "Default")
      (node (ref "U$3") (pin "17") (pinfunction "17_17") (pintype "passive"))
    )
    (net (code "220") (name "unconnected-(U$4-Pad1)") (class "Default")
      (node (ref "U$4") (pin "1") (pinfunction "1_1") (pintype "passive"))
    )
    (net (code "221") (name "unconnected-(U$4-Pad2)") (class "Default")
      (node (ref "U$4") (pin "2") (pinfunction "2_2") (pintype "passive"))
    )
    (net (code "222") (name "unconnected-(U$4-Pad3)") (class "Default")
      (node (ref "U$4") (pin "3") (pinfunction "3_3") (pintype "passive"))
    )
    (net (code "223") (name "unconnected-(U$4-Pad4)") (class "Default")
      (node (ref "U$4") (pin "4") (pinfunction "4_4") (pintype "passive"))
    )
    (net (code "224") (name "unconnected-(U$4-Pad5)") (class "Default")
      (node (ref "U$4") (pin "5") (pinfunction "5_5") (pintype "passive"))
    )
    (net (code "225") (name "unconnected-(U$4-Pad6)") (class "Default")
      (node (ref "U$4") (pin "6") (pinfunction "6_6") (pintype "passive"))
    )
    (net (code "226") (name "unconnected-(U$4-Pad7)") (class "Default")
      (node (ref "U$4") (pin "7") (pinfunction "7_7") (pintype "passive"))
    )
    (net (code "227") (name "unconnected-(U$4-Pad8)") (class "Default")
      (node (ref "U$4") (pin "8") (pinfunction "8_8") (pintype "passive"))
    )
    (net (code "228") (name "unconnected-(U$4-Pad9)") (class "Default")
      (node (ref "U$4") (pin "9") (pinfunction "9_9") (pintype "passive"))
    )
    (net (code "229") (name "unconnected-(U$4-Pad10)") (class "Default")
      (node (ref "U$4") (pin "10") (pinfunction "10_10") (pintype "passive"))
    )
    (net (code "230") (name "unconnected-(U$4-Pad11)") (class "Default")
      (node (ref "U$4") (pin "11") (pinfunction "11_11") (pintype "passive"))
    )
    (net (code "231") (name "unconnected-(U$4-Pad12)") (class "Default")
      (node (ref "U$4") (pin "12") (pinfunction "12_12") (pintype "passive"))
    )
    (net (code "232") (name "unconnected-(U$4-Pad13)") (class "Default")
      (node (ref "U$4") (pin "13") (pinfunction "13_13") (pintype "passive"))
    )
    (net (code "233") (name "unconnected-(U$4-Pad14)") (class "Default")
      (node (ref "U$4") (pin "14") (pinfunction "14_14") (pintype "passive"))
    )
    (net (code "234") (name "unconnected-(U$4-Pad15)") (class "Default")
      (node (ref "U$4") (pin "15") (pinfunction "15_15") (pintype "passive"))
    )
    (net (code "235") (name "unconnected-(U$4-Pad16)") (class "Default")
      (node (ref "U$4") (pin "16") (pinfunction "16_16") (pintype "passive"))
    )
    (net (code "236") (name "unconnected-(U$4-Pad17)") (class "Default")
      (node (ref "U$4") (pin "17") (pinfunction "17_17") (pintype "passive"))
    )
    (net (code "237") (name "unconnected-(U$5-Pad1)") (class "Default")
      (node (ref "U$5") (pin "1") (pinfunction "1_1") (pintype "passive"))
    )
    (net (code "238") (name "unconnected-(U$5-Pad2)") (class "Default")
      (node (ref "U$5") (pin "2") (pinfunction "2_2") (pintype "passive"))
    )
    (net (code "239") (name "unconnected-(U$5-Pad3)") (class "Default")
      (node (ref "U$5") (pin "3") (pinfunction "3_3") (pintype "passive"))
    )
    (net (code "240") (name "unconnected-(U$5-Pad4)") (class "Default")
      (node (ref "U$5") (pin "4") (pinfunction "4_4") (pintype "passive"))
    )
    (net (code "241") (name "unconnected-(U$5-Pad5)") (class "Default")
      (node (ref "U$5") (pin "5") (pinfunction "5_5") (pintype "passive"))
    )
    (net (code "242") (name "unconnected-(U$5-Pad6)") (class "Default")
      (node (ref "U$5") (pin "6") (pinfunction "6_6") (pintype "passive"))
    )
    (net (code "243") (name "unconnected-(U$5-Pad7)") (class "Default")
      (node (ref "U$5") (pin "7") (pinfunction "7_7") (pintype "passive"))
    )
    (net (code "244") (name "unconnected-(U$5-Pad8)") (class "Default")
      (node (ref "U$5") (pin "8") (pinfunction "8_8") (pintype "passive"))
    )
    (net (code "245") (name "unconnected-(U$5-Pad9)") (class "Default")
      (node (ref "U$5") (pin "9") (pinfunction "9_9") (pintype "passive"))
    )
    (net (code "246") (name "unconnected-(U$5-Pad10)") (class "Default")
      (node (ref "U$5") (pin "10") (pinfunction "10_10") (pintype "passive"))
    )
    (net (code "247") (name "unconnected-(U$5-Pad11)") (class "Default")
      (node (ref "U$5") (pin "11") (pinfunction "11_11") (pintype "passive"))
    )
    (net (code "248") (name "unconnected-(U$5-Pad12)") (class "Default")
      (node (ref "U$5") (pin "12") (pinfunction "12_12") (pintype "passive"))
    )
    (net (code "249") (name "unconnected-(U$5-Pad13)") (class "Default")
      (node (ref "U$5") (pin "13") (pinfunction "13_13") (pintype "passive"))
    )
    (net (code "250") (name "unconnected-(U$5-Pad14)") (class "Default")
      (node (ref "U$5") (pin "14") (pinfunction "14_14") (pintype "passive"))
    )
    (net (code "251") (name "unconnected-(U$5-Pad15)") (class "Default")
      (node (ref "U$5") (pin "15") (pinfunction "15_15") (pintype "passive"))
    )
    (net (code "252") (name "unconnected-(U$5-Pad16)") (class "Default")
      (node (ref "U$5") (pin "16") (pinfunction "16_16") (pintype "passive"))
    )
    (net (code "253") (name "unconnected-(U$5-Pad17)") (class "Default")
      (node (ref "U$5") (pin "17") (pinfunction "17_17") (pintype "passive"))
    )
    (net (code "254") (name "unconnected-(U$6-Pad1)") (class "Default")
      (node (ref "U$6") (pin "1") (pinfunction "1_1") (pintype "passive"))
    )
    (net (code "255") (name "unconnected-(U$6-Pad2)") (class "Default")
      (node (ref "U$6") (pin "2") (pinfunction "2_2") (pintype "passive"))
    )
    (net (code "256") (name "unconnected-(U$6-Pad3)") (class "Default")
      (node (ref "U$6") (pin "3") (pinfunction "3_3") (pintype "passive"))
    )
    (net (code "257") (name "unconnected-(U$6-Pad4)") (class "Default")
      (node (ref "U$6") (pin "4") (pinfunction "4_4") (pintype "passive"))
    )
    (net (code "258") (name "unconnected-(U$6-Pad5)") (class "Default")
      (node (ref "U$6") (pin "5") (pinfunction "5_5") (pintype "passive"))
    )
    (net (code "259") (name "unconnected-(U$6-Pad6)") (class "Default")
      (node (ref "U$6") (pin "6") (pinfunction "6_6") (pintype "passive"))
    )
    (net (code "260") (name "unconnected-(U$6-Pad7)") (class "Default")
      (node (ref "U$6") (pin "7") (pinfunction "7_7") (pintype "passive"))
    )
    (net (code "261") (name "unconnected-(U$6-Pad8)") (class "Default")
      (node (ref "U$6") (pin "8") (pinfunction "8_8") (pintype "passive"))
    )
    (net (code "262") (name "unconnected-(U$6-Pad9)") (class "Default")
      (node (ref "U$6") (pin "9") (pinfunction "9_9") (pintype "passive"))
    )
    (net (code "263") (name "unconnected-(U$6-Pad10)") (class "Default")
      (node (ref "U$6") (pin "10") (pinfunction "10_10") (pintype "passive"))
    )
    (net (code "264") (name "unconnected-(U$6-Pad11)") (class "Default")
      (node (ref "U$6") (pin "11") (pinfunction "11_11") (pintype "passive"))
    )
    (net (code "265") (name "unconnected-(U$6-Pad12)") (class "Default")
      (node (ref "U$6") (pin "12") (pinfunction "12_12") (pintype "passive"))
    )
    (net (code "266") (name "unconnected-(U$6-Pad13)") (class "Default")
      (node (ref "U$6") (pin "13") (pinfunction "13_13") (pintype "passive"))
    )
    (net (code "267") (name "unconnected-(U$6-Pad14)") (class "Default")
      (node (ref "U$6") (pin "14") (pinfunction "14_14") (pintype "passive"))
    )
    (net (code "268") (name "unconnected-(U$6-Pad15)") (class "Default")
      (node (ref "U$6") (pin "15") (pinfunction "15_15") (pintype "passive"))
    )
    (net (code "269") (name "unconnected-(U$6-Pad16)") (class "Default")
      (node (ref "U$6") (pin "16") (pinfunction "16_16") (pintype "passive"))
    )
    (net (code "270") (name "unconnected-(U$6-Pad17)") (class "Default")
      (node (ref "U$6") (pin "17") (pinfunction "17_17") (pintype "passive"))
    )
    (net (code "271") (name "unconnected-(U$7-Pad1)") (class "Default")
      (node (ref "U$7") (pin "1") (pinfunction "1_1") (pintype "passive"))
    )
    (net (code "272") (name "unconnected-(U$7-Pad2)") (class "Default")
      (node (ref "U$7") (pin "2") (pinfunction "2_2") (pintype "passive"))
    )
    (net (code "273") (name "unconnected-(U$7-Pad3)") (class "Default")
      (node (ref "U$7") (pin "3") (pinfunction "3_3") (pintype "passive"))
    )
    (net (code "274") (name "unconnected-(U$7-Pad4)") (class "Default")
      (node (ref "U$7") (pin "4") (pinfunction "4_4") (pintype "passive"))
    )
    (net (code "275") (name "unconnected-(U$7-Pad5)") (class "Default")
      (node (ref "U$7") (pin "5") (pinfunction "5_5") (pintype "passive"))
    )
    (net (code "276") (name "unconnected-(U$7-Pad6)") (class "Default")
      (node (ref "U$7") (pin "6") (pinfunction "6_6") (pintype "passive"))
    )
    (net (code "277") (name "unconnected-(U$7-Pad7)") (class "Default")
      (node (ref "U$7") (pin "7") (pinfunction "7_7") (pintype "passive"))
    )
    (net (code "278") (name "unconnected-(U$7-Pad8)") (class "Default")
      (node (ref "U$7") (pin "8") (pinfunction "8_8") (pintype "passive"))
    )
    (net (code "279") (name "unconnected-(U$7-Pad9)") (class "Default")
      (node (ref "U$7") (pin "9") (pinfunction "9_9") (pintype "passive"))
    )
    (net (code "280") (name "unconnected-(U$7-Pad10)") (class "Default")
      (node (ref "U$7") (pin "10") (pinfunction "10_10") (pintype "passive"))
    )
    (net (code "281") (name "unconnected-(U$7-Pad11)") (class "Default")
      (node (ref "U$7") (pin "11") (pinfunction "11_11") (pintype "passive"))
    )
    (net (code "282") (name "unconnected-(U$7-Pad12)") (class "Default")
      (node (ref "U$7") (pin "12") (pinfunction "12_12") (pintype "passive"))
    )
    (net (code "283") (name "unconnected-(U$7-Pad13)") (class "Default")
      (node (ref "U$7") (pin "13") (pinfunction "13_13") (pintype "passive"))
    )
    (net (code "284") (name "unconnected-(U$7-Pad14)") (class "Default")
      (node (ref "U$7") (pin "14") (pinfunction "14_14") (pintype "passive"))
    )
    (net (code "285") (name "unconnected-(U$7-Pad15)") (class "Default")
      (node (ref "U$7") (pin "15") (pinfunction "15_15") (pintype "passive"))
    )
    (net (code "286") (name "unconnected-(U$7-Pad16)") (class "Default")
      (node (ref "U$7") (pin "16") (pinfunction "16_16") (pintype "passive"))
    )
    (net (code "287") (name "unconnected-(U$7-Pad17)") (class "Default")
      (node (ref "U$7") (pin "17") (pinfunction "17_17") (pintype "passive"))
    )
    (net (code "288") (name "unconnected-(U$8-Pad1)") (class "Default")
      (node (ref "U$8") (pin "1") (pinfunction "1_1") (pintype "passive"))
    )
    (net (code "289") (name "unconnected-(U$8-Pad2)") (class "Default")
      (node (ref "U$8") (pin "2") (pinfunction "2_2") (pintype "passive"))
    )
    (net (code "290") (name "unconnected-(U$8-Pad3)") (class "Default")
      (node (ref "U$8") (pin "3") (pinfunction "3_3") (pintype "passive"))
    )
    (net (code "291") (name "unconnected-(U$8-Pad4)") (class "Default")
      (node (ref "U$8") (pin "4") (pinfunction "4_4") (pintype "passive"))
    )
    (net (code "292") (name "unconnected-(U$8-Pad5)") (class "Default")
      (node (ref "U$8") (pin "5") (pinfunction "5_5") (pintype "passive"))
    )
    (net (code "293") (name "unconnected-(U$8-Pad6)") (class "Default")
      (node (ref "U$8") (pin "6") (pinfunction "6_6") (pintype "passive"))
    )
    (net (code "294") (name "unconnected-(U$8-Pad7)") (class "Default")
      (node (ref "U$8") (pin "7") (pinfunction "7_7") (pintype "passive"))
    )
    (net (code "295") (name "unconnected-(U$8-Pad8)") (class "Default")
      (node (ref "U$8") (pin "8") (pinfunction "8_8") (pintype "passive"))
    )
    (net (code "296") (name "unconnected-(U$8-Pad9)") (class "Default")
      (node (ref "U$8") (pin "9") (pinfunction "9_9") (pintype "passive"))
    )
    (net (code "297") (name "unconnected-(U$8-Pad10)") (class "Default")
      (node (ref "U$8") (pin "10") (pinfunction "10_10") (pintype "passive"))
    )
    (net (code "298") (name "unconnected-(U$8-Pad11)") (class "Default")
      (node (ref "U$8") (pin "11") (pinfunction "11_11") (pintype "passive"))
    )
    (net (code "299") (name "unconnected-(U$8-Pad12)") (class "Default")
      (node (ref "U$8") (pin "12") (pinfunction "12_12") (pintype "passive"))
    )
    (net (code "300") (name "unconnected-(U$8-Pad13)") (class "Default")
      (node (ref "U$8") (pin "13") (pinfunction "13_13") (pintype "passive"))
    )
    (net (code "301") (name "unconnected-(U$8-Pad14)") (class "Default")
      (node (ref "U$8") (pin "14") (pinfunction "14_14") (pintype "passive"))
    )
    (net (code "302") (name "unconnected-(U$8-Pad15)") (class "Default")
      (node (ref "U$8") (pin "15") (pinfunction "15_15") (pintype "passive"))
    )
    (net (code "303") (name "unconnected-(U$8-Pad16)") (class "Default")
      (node (ref "U$8") (pin "16") (pinfunction "16_16") (pintype "passive"))
    )
    (net (code "304") (name "unconnected-(U$8-Pad17)") (class "Default")
      (node (ref "U$8") (pin "17") (pinfunction "17_17") (pintype "passive"))
    )
    (net (code "305") (name "unconnected-(U$10-Pad1)") (class "Default")
      (node (ref "U$10") (pin "1") (pinfunction "1_1") (pintype "passive"))
    )
    (net (code "306") (name "unconnected-(U$10-Pad2)") (class "Default")
      (node (ref "U$10") (pin "2") (pinfunction "2_2") (pintype "passive"))
    )
    (net (code "307") (name "unconnected-(U$10-Pad3)") (class "Default")
      (node (ref "U$10") (pin "3") (pinfunction "3_3") (pintype "passive"))
    )
    (net (code "308") (name "unconnected-(U$10-Pad4)") (class "Default")
      (node (ref "U$10") (pin "4") (pinfunction "4_4") (pintype "passive"))
    )
    (net (code "309") (name "unconnected-(U$10-Pad5)") (class "Default")
      (node (ref "U$10") (pin "5") (pinfunction "5_5") (pintype "passive"))
    )
    (net (code "310") (name "unconnected-(U$10-Pad6)") (class "Default")
      (node (ref "U$10") (pin "6") (pinfunction "6_6") (pintype "passive"))
    )
    (net (code "311") (name "unconnected-(U$10-Pad7)") (class "Default")
      (node (ref "U$10") (pin "7") (pinfunction "7_7") (pintype "passive"))
    )
    (net (code "312") (name "unconnected-(U$10-Pad8)") (class "Default")
      (node (ref "U$10") (pin "8") (pinfunction "8_8") (pintype "passive"))
    )
    (net (code "313") (name "unconnected-(U$10-Pad9)") (class "Default")
      (node (ref "U$10") (pin "9") (pinfunction "9_9") (pintype "passive"))
    )
    (net (code "314") (name "unconnected-(U$10-Pad10)") (class "Default")
      (node (ref "U$10") (pin "10") (pinfunction "10_10") (pintype "passive"))
    )
    (net (code "315") (name "unconnected-(U$10-Pad11)") (class "Default")
      (node (ref "U$10") (pin "11") (pinfunction "11_11") (pintype "passive"))
    )
    (net (code "316") (name "unconnected-(U$10-Pad12)") (class "Default")
      (node (ref "U$10") (pin "12") (pinfunction "12_12") (pintype "passive"))
    )
    (net (code "317") (name "unconnected-(U$10-Pad13)") (class "Default")
      (node (ref "U$10") (pin "13") (pinfunction "13_13") (pintype "passive"))
    )
    (net (code "318") (name "unconnected-(U$10-Pad14)") (class "Default")
      (node (ref "U$10") (pin "14") (pinfunction "14_14") (pintype "passive"))
    )
    (net (code "319") (name "unconnected-(U$10-Pad15)") (class "Default")
      (node (ref "U$10") (pin "15") (pinfunction "15_15") (pintype "passive"))
    )
    (net (code "320") (name "unconnected-(U$10-Pad16)") (class "Default")
      (node (ref "U$10") (pin "16") (pinfunction "16_16") (pintype "passive"))
    )
    (net (code "321") (name "unconnected-(U$10-Pad17)") (class "Default")
      (node (ref "U$10") (pin "17") (pinfunction "17_17") (pintype "passive"))
    )
    (net (code "322") (name "unconnected-(U$11-Pad1)") (class "Default")
      (node (ref "U$11") (pin "1") (pinfunction "1_1") (pintype "passive"))
    )
    (net (code "323") (name "unconnected-(U$11-Pad2)") (class "Default")
      (node (ref "U$11") (pin "2") (pinfunction "2_2") (pintype "passive"))
    )
    (net (code "324") (name "unconnected-(U$11-Pad3)") (class "Default")
      (node (ref "U$11") (pin "3") (pinfunction "3_3") (pintype "passive"))
    )
    (net (code "325") (name "unconnected-(U$11-Pad4)") (class "Default")
      (node (ref "U$11") (pin "4") (pinfunction "4_4") (pintype "passive"))
    )
    (net (code "326") (name "unconnected-(U$11-Pad5)") (class "Default")
      (node (ref "U$11") (pin "5") (pinfunction "5_5") (pintype "passive"))
    )
    (net (code "327") (name "unconnected-(U$11-Pad6)") (class "Default")
      (node (ref "U$11") (pin "6") (pinfunction "6_6") (pintype "passive"))
    )
    (net (code "328") (name "unconnected-(U$11-Pad7)") (class "Default")
      (node (ref "U$11") (pin "7") (pinfunction "7_7") (pintype "passive"))
    )
    (net (code "329") (name "unconnected-(U$11-Pad8)") (class "Default")
      (node (ref "U$11") (pin "8") (pinfunction "8_8") (pintype "passive"))
    )
    (net (code "330") (name "unconnected-(U$11-Pad9)") (class "Default")
      (node (ref "U$11") (pin "9") (pinfunction "9_9") (pintype "passive"))
    )
    (net (code "331") (name "unconnected-(U$11-Pad10)") (class "Default")
      (node (ref "U$11") (pin "10") (pinfunction "10_10") (pintype "passive"))
    )
    (net (code "332") (name "unconnected-(U$11-Pad11)") (class "Default")
      (node (ref "U$11") (pin "11") (pinfunction "11_11") (pintype "passive"))
    )
    (net (code "333") (name "unconnected-(U$11-Pad12)") (class "Default")
      (node (ref "U$11") (pin "12") (pinfunction "12_12") (pintype "passive"))
    )
    (net (code "334") (name "unconnected-(U$11-Pad13)") (class "Default")
      (node (ref "U$11") (pin "13") (pinfunction "13_13") (pintype "passive"))
    )
    (net (code "335") (name "unconnected-(U$11-Pad14)") (class "Default")
      (node (ref "U$11") (pin "14") (pinfunction "14_14") (pintype "passive"))
    )
    (net (code "336") (name "unconnected-(U$11-Pad15)") (class "Default")
      (node (ref "U$11") (pin "15") (pinfunction "15_15") (pintype "passive"))
    )
    (net (code "337") (name "unconnected-(U$11-Pad16)") (class "Default")
      (node (ref "U$11") (pin "16") (pinfunction "16_16") (pintype "passive"))
    )
    (net (code "338") (name "unconnected-(U$11-Pad17)") (class "Default")
      (node (ref "U$11") (pin "17") (pinfunction "17_17") (pintype "passive"))
    )
    (net (code "339") (name "unconnected-(U$12-Pad1)") (class "Default")
      (node (ref "U$12") (pin "1") (pinfunction "1_1") (pintype "passive"))
    )
    (net (code "340") (name "unconnected-(U$12-Pad2)") (class "Default")
      (node (ref "U$12") (pin "2") (pinfunction "2_2") (pintype "passive"))
    )
    (net (code "341") (name "unconnected-(U$12-Pad3)") (class "Default")
      (node (ref "U$12") (pin "3") (pinfunction "3_3") (pintype "passive"))
    )
    (net (code "342") (name "unconnected-(U$12-Pad4)") (class "Default")
      (node (ref "U$12") (pin "4") (pinfunction "4_4") (pintype "passive"))
    )
    (net (code "343") (name "unconnected-(U$12-Pad5)") (class "Default")
      (node (ref "U$12") (pin "5") (pinfunction "5_5") (pintype "passive"))
    )
    (net (code "344") (name "unconnected-(U$12-Pad6)") (class "Default")
      (node (ref "U$12") (pin "6") (pinfunction "6_6") (pintype "passive"))
    )
    (net (code "345") (name "unconnected-(U$12-Pad7)") (class "Default")
      (node (ref "U$12") (pin "7") (pinfunction "7_7") (pintype "passive"))
    )
    (net (code "346") (name "unconnected-(U$12-Pad8)") (class "Default")
      (node (ref "U$12") (pin "8") (pinfunction "8_8") (pintype "passive"))
    )
    (net (code "347") (name "unconnected-(U$12-Pad9)") (class "Default")
      (node (ref "U$12") (pin "9") (pinfunction "9_9") (pintype "passive"))
    )
    (net (code "348") (name "unconnected-(U$12-Pad10)") (class "Default")
      (node (ref "U$12") (pin "10") (pinfunction "10_10") (pintype "passive"))
    )
    (net (code "349") (name "unconnected-(U$12-Pad11)") (class "Default")
      (node (ref "U$12") (pin "11") (pinfunction "11_11") (pintype "passive"))
    )
    (net (code "350") (name "unconnected-(U$12-Pad12)") (class "Default")
      (node (ref "U$12") (pin "12") (pinfunction "12_12") (pintype "passive"))
    )
    (net (code "351") (name "unconnected-(U$12-Pad13)") (class "Default")
      (node (ref "U$12") (pin "13") (pinfunction "13_13") (pintype "passive"))
    )
    (net (code "352") (name "unconnected-(U$12-Pad14)") (class "Default")
      (node (ref "U$12") (pin "14") (pinfunction "14_14") (pintype "passive"))
    )
    (net (code "353") (name "unconnected-(U$12-Pad15)") (class "Default")
      (node (ref "U$12") (pin "15") (pinfunction "15_15") (pintype "passive"))
    )
    (net (code "354") (name "unconnected-(U$12-Pad16)") (class "Default")
      (node (ref "U$12") (pin "16") (pinfunction "16_16") (pintype "passive"))
    )
    (net (code "355") (name "unconnected-(U$12-Pad17)") (class "Default")
      (node (ref "U$12") (pin "17") (pinfunction "17_17") (pintype "passive"))
    )
    (net (code "356") (name "unconnected-(U$13-Pad1)") (class "Default")
      (node (ref "U$13") (pin "1") (pinfunction "1_1") (pintype "passive"))
    )
    (net (code "357") (name "unconnected-(U$13-Pad2)") (class "Default")
      (node (ref "U$13") (pin "2") (pinfunction "2_2") (pintype "passive"))
    )
    (net (code "358") (name "unconnected-(U$13-Pad3)") (class "Default")
      (node (ref "U$13") (pin "3") (pinfunction "3_3") (pintype "passive"))
    )
    (net (code "359") (name "unconnected-(U$13-Pad4)") (class "Default")
      (node (ref "U$13") (pin "4") (pinfunction "4_4") (pintype "passive"))
    )
    (net (code "360") (name "unconnected-(U$13-Pad5)") (class "Default")
      (node (ref "U$13") (pin "5") (pinfunction "5_5") (pintype "passive"))
    )
    (net (code "361") (name "unconnected-(U$13-Pad6)") (class "Default")
      (node (ref "U$13") (pin "6") (pinfunction "6_6") (pintype "passive"))
    )
    (net (code "362") (name "unconnected-(U$13-Pad7)") (class "Default")
      (node (ref "U$13") (pin "7") (pinfunction "7_7") (pintype "passive"))
    )
    (net (code "363") (name "unconnected-(U$13-Pad8)") (class "Default")
      (node (ref "U$13") (pin "8") (pinfunction "8_8") (pintype "passive"))
    )
    (net (code "364") (name "unconnected-(U$13-Pad9)") (class "Default")
      (node (ref "U$13") (pin "9") (pinfunction "9_9") (pintype "passive"))
    )
    (net (code "365") (name "unconnected-(U$13-Pad10)") (class "Default")
      (node (ref "U$13") (pin "10") (pinfunction "10_10") (pintype "passive"))
    )
    (net (code "366") (name "unconnected-(U$13-Pad11)") (class "Default")
      (node (ref "U$13") (pin "11") (pinfunction "11_11") (pintype "passive"))
    )
    (net (code "367") (name "unconnected-(U$13-Pad12)") (class "Default")
      (node (ref "U$13") (pin "12") (pinfunction "12_12") (pintype "passive"))
    )
    (net (code "368") (name "unconnected-(U$13-Pad13)") (class "Default")
      (node (ref "U$13") (pin "13") (pinfunction "13_13") (pintype "passive"))
    )
    (net (code "369") (name "unconnected-(U$13-Pad14)") (class "Default")
      (node (ref "U$13") (pin "14") (pinfunction "14_14") (pintype "passive"))
    )
    (net (code "370") (name "unconnected-(U$13-Pad15)") (class "Default")
      (node (ref "U$13") (pin "15") (pinfunction "15_15") (pintype "passive"))
    )
    (net (code "371") (name "unconnected-(U$13-Pad16)") (class "Default")
      (node (ref "U$13") (pin "16") (pinfunction "16_16") (pintype "passive"))
    )
    (net (code "372") (name "unconnected-(U$13-Pad17)") (class "Default")
      (node (ref "U$13") (pin "17") (pinfunction "17_17") (pintype "passive"))
    )
    (net (code "373") (name "unconnected-(U1-GND-PadGND@1)") (class "Default")
      (node (ref "U1") (pin "GND@1") (pinfunction "GND_GND@1") (pintype "bidirectional"))
    )
    (net (code "374") (name "unconnected-(U1-GND-PadGND@2)") (class "Default")
      (node (ref "U1") (pin "GND@2") (pinfunction "GND_GND@2") (pintype "bidirectional"))
    )
    (net (code "375") (name "unconnected-(U1-Pad3.3V)") (class "Default")
      (node (ref "U1") (pin "3.3V") (pinfunction "3.3V_3.3V") (pintype "bidirectional"))
    )
    (net (code "376") (name "unconnected-(U1-PadA0)") (class "Default")
      (node (ref "U1") (pin "A0") (pinfunction "A0_A0") (pintype "bidirectional"))
    )
    (net (code "377") (name "unconnected-(U1-PadA1)") (class "Default")
      (node (ref "U1") (pin "A1") (pinfunction "A1_A1") (pintype "bidirectional"))
    )
    (net (code "378") (name "unconnected-(U1-PadA2)") (class "Default")
      (node (ref "U1") (pin "A2") (pinfunction "A2_A2") (pintype "bidirectional"))
    )
    (net (code "379") (name "unconnected-(U1-PadA3)") (class "Default")
      (node (ref "U1") (pin "A3") (pinfunction "A3_A3") (pintype "bidirectional"))
    )
    (net (code "380") (name "unconnected-(U1-PadA4)") (class "Default")
      (node (ref "U1") (pin "A4") (pinfunction "A4_A4") (pintype "bidirectional"))
    )
    (net (code "381") (name "unconnected-(U1-PadA5)") (class "Default")
      (node (ref "U1") (pin "A5") (pinfunction "A5_A5") (pintype "bidirectional"))
    )
    (net (code "382") (name "unconnected-(U1-PadAREF)") (class "Default")
      (node (ref "U1") (pin "AREF") (pinfunction "AREF_AREF") (pintype "bidirectional"))
    )
    (net (code "383") (name "unconnected-(U1-PadRES)") (class "Default")
      (node (ref "U1") (pin "RES") (pinfunction "RES_RES") (pintype "bidirectional"))
    )
    (net (code "384") (name "unconnected-(U1-PadVIN)") (class "Default")
      (node (ref "U1") (pin "VIN") (pinfunction "VIN_VIN") (pintype "bidirectional"))
    )
  )
)
